# USB3_0.net
KiCad netlist of a schematic drawn in Altium Designer
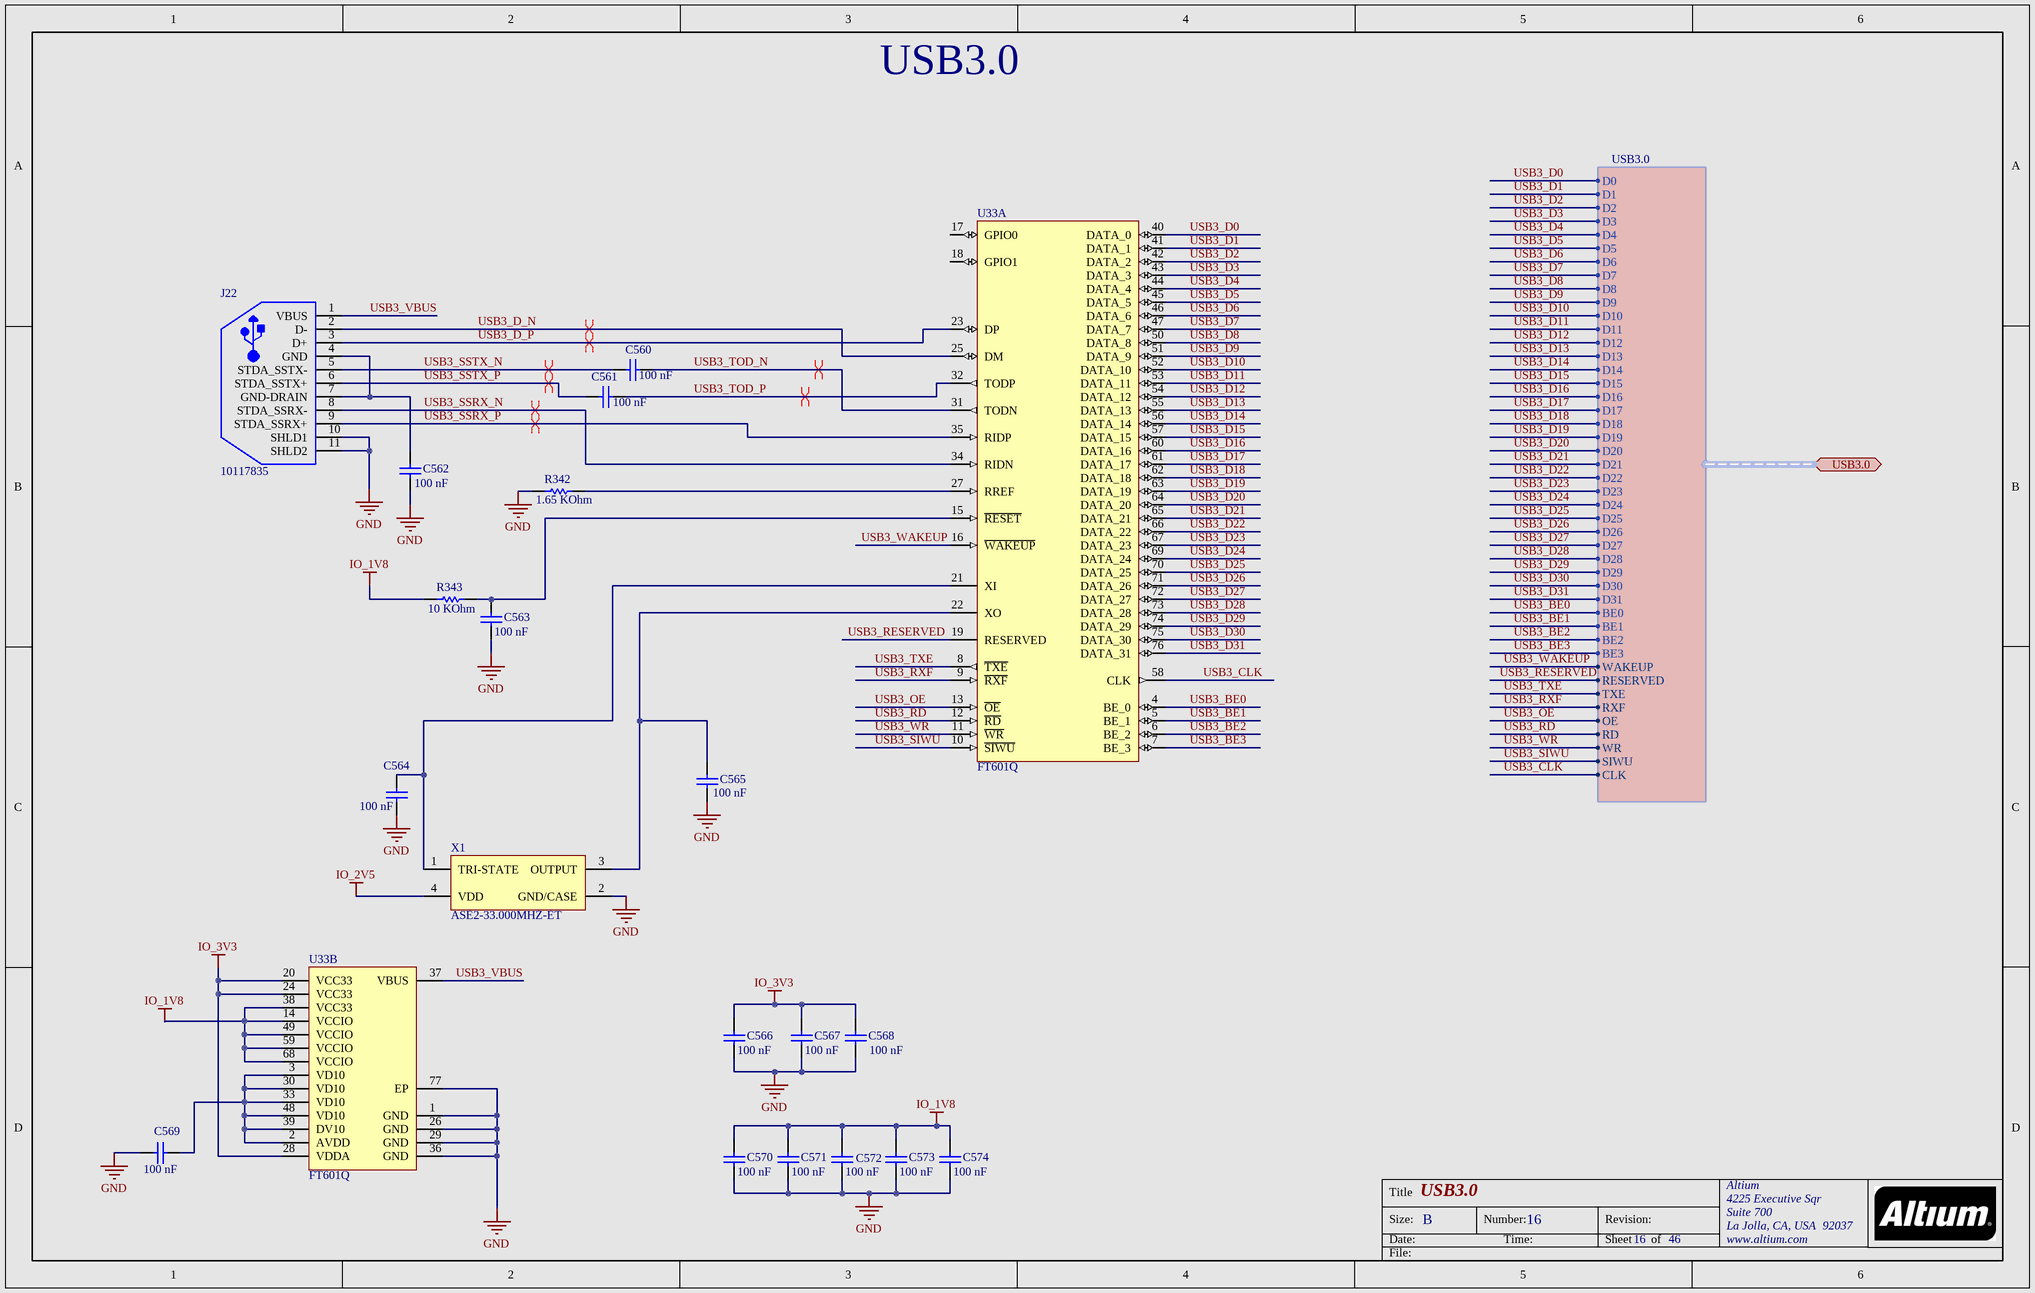
[diagram p0: USB3.0.SchDoc]

(export (version "E")
  (design (tool "Eeschema 10.0.6"))
  (components
    (comp (ref "C560")
      (value "GRM033R60J104KE19D")
      (footprint "CAPC0603X33X15LL03T05")
      (description "Chip Capacitor, 100 nF, +/- 10%, 6.3 V, -55 to 85 degC, 0201 (0603 Metric), RoHS, Tape and Reel")
      (fields
        (field (name "TOLERANCE") "10%")
        (field (name "CAPACITANCE") "100 nF")
        (field (name "MANUFACTURER") "Basic Passives")
      )
      (libsource (lib "Altium Content Vault") (part "CAP-NP-2"))
    )
    (comp (ref "C561")
      (value "GRM033R60J104KE19D")
      (footprint "CAPC0603X33X15LL03T05")
      (description "Chip Capacitor, 100 nF, +/- 10%, 6.3 V, -55 to 85 degC, 0201 (0603 Metric), RoHS, Tape and Reel")
      (fields
        (field (name "TOLERANCE") "10%")
        (field (name "CAPACITANCE") "100 nF")
        (field (name "MANUFACTURER") "Basic Passives")
      )
      (libsource (lib "Altium Content Vault") (part "CAP-NP-2"))
    )
    (comp (ref "C562")
      (value "GRM033R60J104KE19D")
      (footprint "CAPC0603X33X15LL03T05")
      (description "Chip Capacitor, 100 nF, +/- 10%, 6.3 V, -55 to 85 degC, 0201 (0603 Metric), RoHS, Tape and Reel")
      (fields
        (field (name "TOLERANCE") "10%")
        (field (name "CAPACITANCE") "100 nF")
        (field (name "MANUFACTURER") "Basic Passives")
      )
      (libsource (lib "Altium Content Vault") (part "CAP-NP-2"))
    )
    (comp (ref "C563")
      (value "GRM033R60J104KE19D")
      (footprint "CAPC0603X33X15LL03T05")
      (description "Chip Capacitor, 100 nF, +/- 10%, 6.3 V, -55 to 85 degC, 0201 (0603 Metric), RoHS, Tape and Reel")
      (fields
        (field (name "TOLERANCE") "10%")
        (field (name "CAPACITANCE") "100 nF")
        (field (name "MANUFACTURER") "Basic Passives")
      )
      (libsource (lib "Altium Content Vault") (part "CAP-NP-2"))
    )
    (comp (ref "C564")
      (value "GRM033R60J104KE19D")
      (footprint "CAPC0603X33X15LL03T05")
      (description "Chip Capacitor, 100 nF, +/- 10%, 6.3 V, -55 to 85 degC, 0201 (0603 Metric), RoHS, Tape and Reel")
      (fields
        (field (name "TOLERANCE") "10%")
        (field (name "CAPACITANCE") "100 nF")
        (field (name "MANUFACTURER") "Basic Passives")
      )
      (libsource (lib "Altium Content Vault") (part "CAP-NP-2"))
    )
    (comp (ref "C565")
      (value "GRM033R60J104KE19D")
      (footprint "CAPC0603X33X15LL03T05")
      (description "Chip Capacitor, 100 nF, +/- 10%, 6.3 V, -55 to 85 degC, 0201 (0603 Metric), RoHS, Tape and Reel")
      (fields
        (field (name "TOLERANCE") "10%")
        (field (name "CAPACITANCE") "100 nF")
        (field (name "MANUFACTURER") "Basic Passives")
      )
      (libsource (lib "Altium Content Vault") (part "CAP-NP-2"))
    )
    (comp (ref "C566")
      (value "C1005X7R1E104M")
      (footprint "CAPC1005X55X10LL05")
      (description "Chip Capacitor, 0.1 uF, +/- 20%, 25 V, -55 to 125 degC, 0402 (1005 Metric), RoHS, Tape and Reel")
      (fields (field (name "TOLERANCE") "20%") (field (name "CAPACITANCE") "100 nF"))
      (libsource (lib "Altium Content Vault") (part "CAP-NP-2"))
    )
    (comp (ref "C567")
      (value "C1005X7R1E104M")
      (footprint "CAPC1005X55X10LL05")
      (description "Chip Capacitor, 0.1 uF, +/- 20%, 25 V, -55 to 125 degC, 0402 (1005 Metric), RoHS, Tape and Reel")
      (fields (field (name "TOLERANCE") "20%") (field (name "CAPACITANCE") "100 nF"))
      (libsource (lib "Altium Content Vault") (part "CAP-NP-2"))
    )
    (comp (ref "C568")
      (value "C1005X7R1E104M")
      (footprint "CAPC1005X55X10LL05")
      (description "Chip Capacitor, 0.1 uF, +/- 20%, 25 V, -55 to 125 degC, 0402 (1005 Metric), RoHS, Tape and Reel")
      (fields (field (name "TOLERANCE") "20%") (field (name "CAPACITANCE") "100 nF"))
      (libsource (lib "Altium Content Vault") (part "CAP-NP-2"))
    )
    (comp (ref "C569")
      (value "GRM033R60J104KE19D")
      (footprint "CAPC0603X33X15LL03T05")
      (description "Chip Capacitor, 100 nF, +/- 10%, 6.3 V, -55 to 85 degC, 0201 (0603 Metric), RoHS, Tape and Reel")
      (fields
        (field (name "TOLERANCE") "10%")
        (field (name "CAPACITANCE") "100 nF")
        (field (name "MANUFACTURER") "Basic Passives")
      )
      (libsource (lib "Altium Content Vault") (part "CAP-NP-2"))
    )
    (comp (ref "C570")
      (value "C1005X7R1E104M")
      (footprint "CAPC1005X55X10LL05")
      (description "Chip Capacitor, 0.1 uF, +/- 20%, 25 V, -55 to 125 degC, 0402 (1005 Metric), RoHS, Tape and Reel")
      (fields (field (name "TOLERANCE") "20%") (field (name "CAPACITANCE") "100 nF"))
      (libsource (lib "Altium Content Vault") (part "CAP-NP-2"))
    )
    (comp (ref "C571")
      (value "C1005X7R1E104M")
      (footprint "CAPC1005X55X10LL05")
      (description "Chip Capacitor, 0.1 uF, +/- 20%, 25 V, -55 to 125 degC, 0402 (1005 Metric), RoHS, Tape and Reel")
      (fields (field (name "TOLERANCE") "20%") (field (name "CAPACITANCE") "100 nF"))
      (libsource (lib "Altium Content Vault") (part "CAP-NP-2"))
    )
    (comp (ref "C572")
      (value "C1005X7R1E104M")
      (footprint "CAPC1005X55X10LL05")
      (description "Chip Capacitor, 0.1 uF, +/- 20%, 25 V, -55 to 125 degC, 0402 (1005 Metric), RoHS, Tape and Reel")
      (fields (field (name "TOLERANCE") "20%") (field (name "CAPACITANCE") "100 nF"))
      (libsource (lib "Altium Content Vault") (part "CAP-NP-2"))
    )
    (comp (ref "C573")
      (value "C1005X7R1E104M")
      (footprint "CAPC1005X55X10LL05")
      (description "Chip Capacitor, 0.1 uF, +/- 20%, 25 V, -55 to 125 degC, 0402 (1005 Metric), RoHS, Tape and Reel")
      (fields (field (name "TOLERANCE") "20%") (field (name "CAPACITANCE") "100 nF"))
      (libsource (lib "Altium Content Vault") (part "CAP-NP-2"))
    )
    (comp (ref "C574")
      (value "C1005X7R1E104M")
      (footprint "CAPC1005X55X10LL05")
      (description "Chip Capacitor, 0.1 uF, +/- 20%, 25 V, -55 to 125 degC, 0402 (1005 Metric), RoHS, Tape and Reel")
      (fields (field (name "TOLERANCE") "20%") (field (name "CAPACITANCE") "100 nF"))
      (libsource (lib "Altium Content Vault") (part "CAP-NP-2"))
    )
    (comp (ref "J22")
      (value "10117835")
      (footprint "FCI-10117835_V")
      (libsource (lib "Altium Content Vault") (part "CMP-1698-00002-1"))
    )
    (comp (ref "R342")
      (value "ERJ-2RKF1651X")
      (footprint "RESC1005X40X25LL05T05")
      (description "Chip Resistor, 1.65 KOhm, +/- 1%, 100 mW, -55 to 155 degC, 0402 (1005 Metric), RoHS, Tape and Reel")
      (fields
        (field (name "TOLERANCE") "1%")
        (field (name "RESISTANCE") "1.65 KOhm")
        (field (name "MANUFACTURER") "Basic Passives")
      )
      (libsource (lib "Altium Content Vault") (part "RES-2"))
    )
    (comp (ref "R343")
      (value "ERJ-2RKF1002X")
      (footprint "RESC1005X40X25NL05T05")
      (description "Chip Resistor, 10 KOhm, +/- 1%, 100 mW, -55 to 155 degC, 0402 (1005 Metric), RoHS, Tape and Reel")
      (fields
        (field (name "TOLERANCE") "1%")
        (field (name "RESISTANCE") "10 KOhm")
        (field (name "MANUFACTURER") "Basic Passives")
      )
      (libsource (lib "Altium Content Vault") (part "RES-2"))
    )
    (comp (ref "U33")
      (value "FT601Q")
      (footprint "FTDI-QFN-76_M")
      (description "32 Bit USB 3.0 to FIFO Bridge, 5 Gbps, 3 to 3.6 V, -40 to 85 degC, 76-Pin QFN, Pb-Free")
      (libsource (lib "Altium Content Vault") (part "CMP-1723-00001-1"))
    )
    (comp (ref "X1")
      (value "ASE2-33.000MHZ-ET")
      (footprint "ABRA-ASE2_V")
      (fields (field (name "MANUFACTURER") "Abracon"))
      (libsource (lib "Altium Content Vault") (part "CMP-1688-00001-1"))
    )
  )
  (nets
    (net (code "2") (name "/USB3_BE0") (class "Default")
      (node (ref "U33") (pin "4") (pinfunction "BE_0_4") (pintype "bidirectional"))
    )
    (net (code "3") (name "/USB3_BE1") (class "Default")
      (node (ref "U33") (pin "5") (pinfunction "BE_1_5") (pintype "bidirectional"))
    )
    (net (code "4") (name "/USB3_BE2") (class "Default")
      (node (ref "U33") (pin "6") (pinfunction "BE_2_6") (pintype "bidirectional"))
    )
    (net (code "5") (name "/USB3_BE3") (class "Default")
      (node (ref "U33") (pin "7") (pinfunction "BE_3_7") (pintype "bidirectional"))
    )
    (net (code "6") (name "/USB3_CLK") (class "Default")
      (node (ref "U33") (pin "58") (pinfunction "CLK_58") (pintype "output"))
    )
    (net (code "7") (name "/USB3_D0") (class "Default")
      (node (ref "U33") (pin "40") (pinfunction "DATA_0_40") (pintype "bidirectional"))
    )
    (net (code "8") (name "/USB3_D1") (class "Default")
      (node (ref "U33") (pin "41") (pinfunction "DATA_1_41") (pintype "bidirectional"))
    )
    (net (code "9") (name "/USB3_D2") (class "Default")
      (node (ref "U33") (pin "42") (pinfunction "DATA_2_42") (pintype "bidirectional"))
    )
    (net (code "10") (name "/USB3_D3") (class "Default")
      (node (ref "U33") (pin "43") (pinfunction "DATA_3_43") (pintype "bidirectional"))
    )
    (net (code "11") (name "/USB3_D4") (class "Default")
      (node (ref "U33") (pin "44") (pinfunction "DATA_4_44") (pintype "bidirectional"))
    )
    (net (code "12") (name "/USB3_D5") (class "Default")
      (node (ref "U33") (pin "45") (pinfunction "DATA_5_45") (pintype "bidirectional"))
    )
    (net (code "13") (name "/USB3_D6") (class "Default")
      (node (ref "U33") (pin "46") (pinfunction "DATA_6_46") (pintype "bidirectional"))
    )
    (net (code "14") (name "/USB3_D7") (class "Default")
      (node (ref "U33") (pin "47") (pinfunction "DATA_7_47") (pintype "bidirectional"))
    )
    (net (code "15") (name "/USB3_D8") (class "Default")
      (node (ref "U33") (pin "50") (pinfunction "DATA_8_50") (pintype "bidirectional"))
    )
    (net (code "16") (name "/USB3_D9") (class "Default")
      (node (ref "U33") (pin "51") (pinfunction "DATA_9_51") (pintype "bidirectional"))
    )
    (net (code "17") (name "/USB3_D10") (class "Default")
      (node (ref "U33") (pin "52") (pinfunction "DATA_10_52") (pintype "bidirectional"))
    )
    (net (code "18") (name "/USB3_D11") (class "Default")
      (node (ref "U33") (pin "53") (pinfunction "DATA_11_53") (pintype "bidirectional"))
    )
    (net (code "19") (name "/USB3_D12") (class "Default")
      (node (ref "U33") (pin "54") (pinfunction "DATA_12_54") (pintype "bidirectional"))
    )
    (net (code "20") (name "/USB3_D13") (class "Default")
      (node (ref "U33") (pin "55") (pinfunction "DATA_13_55") (pintype "bidirectional"))
    )
    (net (code "21") (name "/USB3_D14") (class "Default")
      (node (ref "U33") (pin "56") (pinfunction "DATA_14_56") (pintype "bidirectional"))
    )
    (net (code "22") (name "/USB3_D15") (class "Default")
      (node (ref "U33") (pin "57") (pinfunction "DATA_15_57") (pintype "bidirectional"))
    )
    (net (code "23") (name "/USB3_D16") (class "Default")
      (node (ref "U33") (pin "60") (pinfunction "DATA_16_60") (pintype "bidirectional"))
    )
    (net (code "24") (name "/USB3_D17") (class "Default")
      (node (ref "U33") (pin "61") (pinfunction "DATA_17_61") (pintype "bidirectional"))
    )
    (net (code "25") (name "/USB3_D18") (class "Default")
      (node (ref "U33") (pin "62") (pinfunction "DATA_18_62") (pintype "bidirectional"))
    )
    (net (code "26") (name "/USB3_D19") (class "Default")
      (node (ref "U33") (pin "63") (pinfunction "DATA_19_63") (pintype "bidirectional"))
    )
    (net (code "27") (name "/USB3_D20") (class "Default")
      (node (ref "U33") (pin "64") (pinfunction "DATA_20_64") (pintype "bidirectional"))
    )
    (net (code "28") (name "/USB3_D21") (class "Default")
      (node (ref "U33") (pin "65") (pinfunction "DATA_21_65") (pintype "bidirectional"))
    )
    (net (code "29") (name "/USB3_D22") (class "Default")
      (node (ref "U33") (pin "66") (pinfunction "DATA_22_66") (pintype "bidirectional"))
    )
    (net (code "30") (name "/USB3_D23") (class "Default")
      (node (ref "U33") (pin "67") (pinfunction "DATA_23_67") (pintype "bidirectional"))
    )
    (net (code "31") (name "/USB3_D24") (class "Default")
      (node (ref "U33") (pin "69") (pinfunction "DATA_24_69") (pintype "bidirectional"))
    )
    (net (code "32") (name "/USB3_D25") (class "Default")
      (node (ref "U33") (pin "70") (pinfunction "DATA_25_70") (pintype "bidirectional"))
    )
    (net (code "33") (name "/USB3_D26") (class "Default")
      (node (ref "U33") (pin "71") (pinfunction "DATA_26_71") (pintype "bidirectional"))
    )
    (net (code "34") (name "/USB3_D27") (class "Default")
      (node (ref "U33") (pin "72") (pinfunction "DATA_27_72") (pintype "bidirectional"))
    )
    (net (code "35") (name "/USB3_D28") (class "Default")
      (node (ref "U33") (pin "73") (pinfunction "DATA_28_73") (pintype "bidirectional"))
    )
    (net (code "36") (name "/USB3_D29") (class "Default")
      (node (ref "U33") (pin "74") (pinfunction "DATA_29_74") (pintype "bidirectional"))
    )
    (net (code "37") (name "/USB3_D30") (class "Default")
      (node (ref "U33") (pin "75") (pinfunction "DATA_30_75") (pintype "bidirectional"))
    )
    (net (code "38") (name "/USB3_D31") (class "Default")
      (node (ref "U33") (pin "76") (pinfunction "DATA_31_76") (pintype "bidirectional"))
    )
    (net (code "39") (name "/USB3_D_N") (class "Default")
      (node (ref "J22") (pin "2") (pinfunction "D-_2") (pintype "passive"))
      (node (ref "U33") (pin "25") (pinfunction "DM_25") (pintype "bidirectional"))
    )
    (net (code "40") (name "/USB3_D_P") (class "Default")
      (node (ref "J22") (pin "3") (pinfunction "D+_3") (pintype "passive"))
      (node (ref "U33") (pin "23") (pinfunction "DP_23") (pintype "bidirectional"))
    )
    (net (code "41") (name "/USB3_OE") (class "Default")
      (node (ref "U33") (pin "13") (pinfunction "~{OE}_13") (pintype "input"))
    )
    (net (code "42") (name "/USB3_RD") (class "Default")
      (node (ref "U33") (pin "12") (pinfunction "~{RD}_12") (pintype "input"))
    )
    (net (code "43") (name "/USB3_RESERVED") (class "Default")
      (node (ref "U33") (pin "19") (pinfunction "RESERVED_19") (pintype "passive"))
    )
    (net (code "44") (name "/USB3_RXF") (class "Default")
      (node (ref "U33") (pin "9") (pinfunction "~{RXF}_9") (pintype "input"))
    )
    (net (code "45") (name "/USB3_SIWU") (class "Default")
      (node (ref "U33") (pin "10") (pinfunction "~{SIWU}_10") (pintype "input"))
    )
    (net (code "46") (name "/USB3_SSRX_N") (class "Default")
      (node (ref "J22") (pin "8") (pinfunction "STDA_SSRX-_8") (pintype "passive"))
      (node (ref "U33") (pin "34") (pinfunction "RIDN_34") (pintype "input"))
    )
    (net (code "47") (name "/USB3_SSRX_P") (class "Default")
      (node (ref "J22") (pin "9") (pinfunction "STDA_SSRX+_9") (pintype "passive"))
      (node (ref "U33") (pin "35") (pinfunction "RIDP_35") (pintype "input"))
    )
    (net (code "48") (name "/USB3_SSTX_N") (class "Default")
      (node (ref "C560") (pin "2") (pinfunction "2_2") (pintype "passive"))
      (node (ref "J22") (pin "5") (pinfunction "STDA_SSTX-_5") (pintype "passive"))
    )
    (net (code "49") (name "/USB3_SSTX_P") (class "Default")
      (node (ref "C561") (pin "2") (pinfunction "2_2") (pintype "passive"))
      (node (ref "J22") (pin "6") (pinfunction "STDA_SSTX+_6") (pintype "passive"))
    )
    (net (code "50") (name "/USB3_TOD_N") (class "Default")
      (node (ref "C560") (pin "1") (pinfunction "1_1") (pintype "passive"))
      (node (ref "U33") (pin "31") (pinfunction "TODN_31") (pintype "output"))
    )
    (net (code "51") (name "/USB3_TOD_P") (class "Default")
      (node (ref "C561") (pin "1") (pinfunction "1_1") (pintype "passive"))
      (node (ref "U33") (pin "32") (pinfunction "TODP_32") (pintype "output"))
    )
    (net (code "52") (name "/USB3_TXE") (class "Default")
      (node (ref "U33") (pin "8") (pinfunction "~{TXE}_8") (pintype "output"))
    )
    (net (code "53") (name "/USB3_VBUS") (class "Default")
      (node (ref "J22") (pin "1") (pinfunction "VBUS_1") (pintype "passive"))
      (node (ref "U33") (pin "37") (pinfunction "VBUS_37") (pintype "power_in"))
    )
    (net (code "54") (name "/USB3_WAKEUP") (class "Default")
      (node (ref "U33") (pin "16") (pinfunction "~{WAKEUP}_16") (pintype "input"))
    )
    (net (code "55") (name "/USB3_WR") (class "Default")
      (node (ref "U33") (pin "11") (pinfunction "~{WR}_11") (pintype "input"))
    )
    (net (code "57") (name "GND") (class "Default")
      (node (ref "C562") (pin "1") (pinfunction "1_1") (pintype "passive"))
      (node (ref "C563") (pin "1") (pinfunction "1_1") (pintype "passive"))
      (node (ref "C564") (pin "1") (pinfunction "1_1") (pintype "passive"))
      (node (ref "C565") (pin "1") (pinfunction "1_1") (pintype "passive"))
      (node (ref "C566") (pin "1") (pinfunction "1_1") (pintype "passive"))
      (node (ref "C567") (pin "1") (pinfunction "1_1") (pintype "passive"))
      (node (ref "C568") (pin "1") (pinfunction "1_1") (pintype "passive"))
      (node (ref "C569") (pin "2") (pinfunction "2_2") (pintype "passive"))
      (node (ref "C570") (pin "1") (pinfunction "1_1") (pintype "passive"))
      (node (ref "C571") (pin "1") (pinfunction "1_1") (pintype "passive"))
      (node (ref "C572") (pin "1") (pinfunction "1_1") (pintype "passive"))
      (node (ref "C573") (pin "1") (pinfunction "1_1") (pintype "passive"))
      (node (ref "C574") (pin "1") (pinfunction "1_1") (pintype "passive"))
      (node (ref "J22") (pin "10") (pinfunction "SHLD1_10") (pintype "passive"))
      (node (ref "J22") (pin "11") (pinfunction "SHLD2_11") (pintype "passive"))
      (node (ref "R342") (pin "2") (pinfunction "2_2") (pintype "passive"))
      (node (ref "U33") (pin "1") (pinfunction "GND_1") (pintype "power_in"))
      (node (ref "U33") (pin "26") (pinfunction "GND_26") (pintype "power_in"))
      (node (ref "U33") (pin "29") (pinfunction "GND_29") (pintype "power_in"))
      (node (ref "U33") (pin "36") (pinfunction "GND_36") (pintype "power_in"))
      (node (ref "U33") (pin "77") (pinfunction "EP_77") (pintype "power_in"))
      (node (ref "X1") (pin "2") (pinfunction "GND/CASE_2") (pintype "power_in"))
    )
    (net (code "58") (name "IO_1V8") (class "Default")
      (node (ref "C570") (pin "2") (pinfunction "2_2") (pintype "passive"))
      (node (ref "C571") (pin "2") (pinfunction "2_2") (pintype "passive"))
      (node (ref "C572") (pin "2") (pinfunction "2_2") (pintype "passive"))
      (node (ref "C573") (pin "2") (pinfunction "2_2") (pintype "passive"))
      (node (ref "C574") (pin "2") (pinfunction "2_2") (pintype "passive"))
      (node (ref "R343") (pin "1") (pinfunction "1_1") (pintype "passive"))
      (node (ref "U33") (pin "14") (pinfunction "VCCIO_14") (pintype "power_in"))
      (node (ref "U33") (pin "38") (pinfunction "VCC33_38") (pintype "power_in"))
      (node (ref "U33") (pin "49") (pinfunction "VCCIO_49") (pintype "power_in"))
      (node (ref "U33") (pin "59") (pinfunction "VCCIO_59") (pintype "power_in"))
      (node (ref "U33") (pin "68") (pinfunction "VCCIO_68") (pintype "power_in"))
    )
    (net (code "59") (name "IO_2V5") (class "Default")
      (node (ref "X1") (pin "4") (pinfunction "VDD_4") (pintype "power_in"))
    )
    (net (code "60") (name "IO_3V3") (class "Default")
      (node (ref "C566") (pin "2") (pinfunction "2_2") (pintype "passive"))
      (node (ref "C567") (pin "2") (pinfunction "2_2") (pintype "passive"))
      (node (ref "C568") (pin "2") (pinfunction "2_2") (pintype "passive"))
      (node (ref "U33") (pin "20") (pinfunction "VCC33_20") (pintype "power_in"))
      (node (ref "U33") (pin "24") (pinfunction "VCC33_24") (pintype "power_in"))
      (node (ref "U33") (pin "28") (pinfunction "VDDA_28") (pintype "power_in"))
    )
    (net (code "61") (name "Net-(J22-GND)") (class "Default")
      (node (ref "C562") (pin "2") (pinfunction "2_2") (pintype "passive"))
      (node (ref "J22") (pin "4") (pinfunction "GND_4") (pintype "passive"))
      (node (ref "J22") (pin "7") (pinfunction "GND-DRAIN_7") (pintype "passive"))
    )
    (net (code "62") (name "Net-(U33A-RREF)") (class "Default")
      (node (ref "R342") (pin "1") (pinfunction "1_1") (pintype "passive"))
      (node (ref "U33") (pin "27") (pinfunction "RREF_27") (pintype "input"))
    )
    (net (code "63") (name "Net-(U33A-XI)") (class "Default")
      (node (ref "C564") (pin "2") (pinfunction "2_2") (pintype "passive"))
      (node (ref "U33") (pin "21") (pinfunction "XI_21") (pintype "passive"))
      (node (ref "X1") (pin "1") (pinfunction "TRI-STATE_1") (pintype "passive"))
    )
    (net (code "64") (name "Net-(U33A-XO)") (class "Default")
      (node (ref "C565") (pin "2") (pinfunction "2_2") (pintype "passive"))
      (node (ref "U33") (pin "22") (pinfunction "XO_22") (pintype "passive"))
      (node (ref "X1") (pin "3") (pinfunction "OUTPUT_3") (pintype "passive"))
    )
    (net (code "65") (name "Net-(U33A-~{RESET})") (class "Default")
      (node (ref "C563") (pin "2") (pinfunction "2_2") (pintype "passive"))
      (node (ref "R343") (pin "2") (pinfunction "2_2") (pintype "passive"))
      (node (ref "U33") (pin "15") (pinfunction "~{RESET}_15") (pintype "input"))
    )
    (net (code "66") (name "Net-(U33B-AVDD)") (class "Default")
      (node (ref "C569") (pin "1") (pinfunction "1_1") (pintype "passive"))
      (node (ref "U33") (pin "2") (pinfunction "AVDD_2") (pintype "power_in"))
      (node (ref "U33") (pin "3") (pinfunction "VD10_3") (pintype "power_in"))
      (node (ref "U33") (pin "30") (pinfunction "VD10_30") (pintype "power_in"))
      (node (ref "U33") (pin "33") (pinfunction "VD10_33") (pintype "power_in"))
      (node (ref "U33") (pin "39") (pinfunction "DV10_39") (pintype "power_in"))
      (node (ref "U33") (pin "48") (pinfunction "VD10_48") (pintype "power_in"))
    )
    (net (code "67") (name "unconnected-(U33A-GPIO0-Pad17)") (class "Default")
      (node (ref "U33") (pin "17") (pinfunction "GPIO0_17") (pintype "bidirectional"))
    )
    (net (code "68") (name "unconnected-(U33A-GPIO1-Pad18)") (class "Default")
      (node (ref "U33") (pin "18") (pinfunction "GPIO1_18") (pintype "bidirectional"))
    )
  )
)
